# EIB32-JAE-HPC-v2.net
KiCad netlist of a schematic drawn in EAGLE
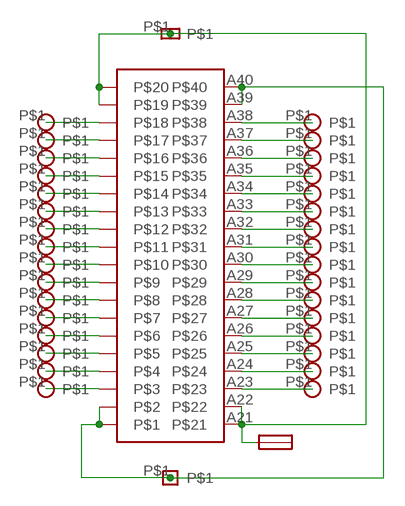
[diagram p0: schematic, sheet 1]

(export (version "E")
  (design (tool "Eeschema 10.0.6"))
  (components
    (comp (ref "U$1")
      (value "WR-40SB-VFH30")
      (footprint "eagle-import:WR-40SB-VFH30")
      (libsource (lib "eagle-import") (part "WR-40SB-VFH30"))
    )
    (comp (ref "U$2")
      (value "EIB-GND-HOLE-PAD-SMALL")
      (footprint "eagle-import:EIB-GND-HOLE-PAD-SMALL")
      (libsource (lib "eagle-import") (part "EIB-GND-HOLE-PAD-SMALL"))
    )
    (comp (ref "U$3")
      (value "EIB-GND-HOLE-PAD")
      (footprint "eagle-import:EIB-GND-HOLE-PAD")
      (libsource (lib "eagle-import") (part "EIB-GND-HOLE-PAD"))
    )
    (comp (ref "U$4")
      (value "JMP-PAD-SMALL")
      (footprint "eagle-import:JMP-PAD-SMALL")
      (libsource (lib "eagle-import") (part "JMP-PAD-SMALL"))
    )
    (comp (ref "U$5")
      (value "EIB-TETRODE-HOLE-RS-PAD")
      (footprint "eagle-import:EIB-TETRODE-HOLE-RS-PAD")
      (libsource (lib "eagle-import") (part "EIB-TETRODE-HOLE-RS-PAD"))
    )
    (comp (ref "U$6")
      (value "EIB-TETRODE-HOLE-RS-PAD")
      (footprint "eagle-import:EIB-TETRODE-HOLE-RS-PAD")
      (libsource (lib "eagle-import") (part "EIB-TETRODE-HOLE-RS-PAD"))
    )
    (comp (ref "U$7")
      (value "EIB-TETRODE-HOLE-RS-PAD")
      (footprint "eagle-import:EIB-TETRODE-HOLE-RS-PAD")
      (libsource (lib "eagle-import") (part "EIB-TETRODE-HOLE-RS-PAD"))
    )
    (comp (ref "U$8")
      (value "EIB-TETRODE-HOLE-RS-PAD")
      (footprint "eagle-import:EIB-TETRODE-HOLE-RS-PAD")
      (libsource (lib "eagle-import") (part "EIB-TETRODE-HOLE-RS-PAD"))
    )
    (comp (ref "U$9")
      (value "EIB-TETRODE-HOLE-RS-PAD")
      (footprint "eagle-import:EIB-TETRODE-HOLE-RS-PAD")
      (libsource (lib "eagle-import") (part "EIB-TETRODE-HOLE-RS-PAD"))
    )
    (comp (ref "U$10")
      (value "EIB-TETRODE-HOLE-RS-PAD")
      (footprint "eagle-import:EIB-TETRODE-HOLE-RS-PAD")
      (libsource (lib "eagle-import") (part "EIB-TETRODE-HOLE-RS-PAD"))
    )
    (comp (ref "U$11")
      (value "EIB-TETRODE-HOLE-RS-PAD")
      (footprint "eagle-import:EIB-TETRODE-HOLE-RS-PAD")
      (libsource (lib "eagle-import") (part "EIB-TETRODE-HOLE-RS-PAD"))
    )
    (comp (ref "U$12")
      (value "EIB-TETRODE-HOLE-RS-PAD")
      (footprint "eagle-import:EIB-TETRODE-HOLE-RS-PAD")
      (libsource (lib "eagle-import") (part "EIB-TETRODE-HOLE-RS-PAD"))
    )
    (comp (ref "U$13")
      (value "EIB-TETRODE-HOLE-RS-PAD")
      (footprint "eagle-import:EIB-TETRODE-HOLE-RS-PAD")
      (libsource (lib "eagle-import") (part "EIB-TETRODE-HOLE-RS-PAD"))
    )
    (comp (ref "U$14")
      (value "EIB-TETRODE-HOLE-RS-PAD")
      (footprint "eagle-import:EIB-TETRODE-HOLE-RS-PAD")
      (libsource (lib "eagle-import") (part "EIB-TETRODE-HOLE-RS-PAD"))
    )
    (comp (ref "U$15")
      (value "EIB-TETRODE-HOLE-RS-PAD")
      (footprint "eagle-import:EIB-TETRODE-HOLE-RS-PAD")
      (libsource (lib "eagle-import") (part "EIB-TETRODE-HOLE-RS-PAD"))
    )
    (comp (ref "U$16")
      (value "EIB-TETRODE-HOLE-RS-PAD")
      (footprint "eagle-import:EIB-TETRODE-HOLE-RS-PAD")
      (libsource (lib "eagle-import") (part "EIB-TETRODE-HOLE-RS-PAD"))
    )
    (comp (ref "U$17")
      (value "EIB-TETRODE-HOLE-RS-PAD")
      (footprint "eagle-import:EIB-TETRODE-HOLE-RS-PAD")
      (libsource (lib "eagle-import") (part "EIB-TETRODE-HOLE-RS-PAD"))
    )
    (comp (ref "U$18")
      (value "EIB-TETRODE-HOLE-RS-PAD")
      (footprint "eagle-import:EIB-TETRODE-HOLE-RS-PAD")
      (libsource (lib "eagle-import") (part "EIB-TETRODE-HOLE-RS-PAD"))
    )
    (comp (ref "U$19")
      (value "EIB-TETRODE-HOLE-RS-PAD")
      (footprint "eagle-import:EIB-TETRODE-HOLE-RS-PAD")
      (libsource (lib "eagle-import") (part "EIB-TETRODE-HOLE-RS-PAD"))
    )
    (comp (ref "U$20")
      (value "EIB-TETRODE-HOLE-RS-PAD")
      (footprint "eagle-import:EIB-TETRODE-HOLE-RS-PAD")
      (libsource (lib "eagle-import") (part "EIB-TETRODE-HOLE-RS-PAD"))
    )
    (comp (ref "U$23")
      (value "EIB-TETRODE-HOLE-RS-PAD")
      (footprint "eagle-import:EIB-TETRODE-HOLE-RS-PAD")
      (libsource (lib "eagle-import") (part "EIB-TETRODE-HOLE-RS-PAD"))
    )
    (comp (ref "U$24")
      (value "EIB-TETRODE-HOLE-RS-PAD")
      (footprint "eagle-import:EIB-TETRODE-HOLE-RS-PAD")
      (libsource (lib "eagle-import") (part "EIB-TETRODE-HOLE-RS-PAD"))
    )
    (comp (ref "U$25")
      (value "EIB-TETRODE-HOLE-RS-PAD")
      (footprint "eagle-import:EIB-TETRODE-HOLE-RS-PAD")
      (libsource (lib "eagle-import") (part "EIB-TETRODE-HOLE-RS-PAD"))
    )
    (comp (ref "U$26")
      (value "EIB-TETRODE-HOLE-RS-PAD")
      (footprint "eagle-import:EIB-TETRODE-HOLE-RS-PAD")
      (libsource (lib "eagle-import") (part "EIB-TETRODE-HOLE-RS-PAD"))
    )
    (comp (ref "U$27")
      (value "EIB-TETRODE-HOLE-RS-PAD")
      (footprint "eagle-import:EIB-TETRODE-HOLE-RS-PAD")
      (libsource (lib "eagle-import") (part "EIB-TETRODE-HOLE-RS-PAD"))
    )
    (comp (ref "U$28")
      (value "EIB-TETRODE-HOLE-RS-PAD")
      (footprint "eagle-import:EIB-TETRODE-HOLE-RS-PAD")
      (libsource (lib "eagle-import") (part "EIB-TETRODE-HOLE-RS-PAD"))
    )
    (comp (ref "U$29")
      (value "EIB-TETRODE-HOLE-RS-PAD")
      (footprint "eagle-import:EIB-TETRODE-HOLE-RS-PAD")
      (libsource (lib "eagle-import") (part "EIB-TETRODE-HOLE-RS-PAD"))
    )
    (comp (ref "U$30")
      (value "EIB-TETRODE-HOLE-RS-PAD")
      (footprint "eagle-import:EIB-TETRODE-HOLE-RS-PAD")
      (libsource (lib "eagle-import") (part "EIB-TETRODE-HOLE-RS-PAD"))
    )
    (comp (ref "U$31")
      (value "EIB-TETRODE-HOLE-RS-PAD")
      (footprint "eagle-import:EIB-TETRODE-HOLE-RS-PAD")
      (libsource (lib "eagle-import") (part "EIB-TETRODE-HOLE-RS-PAD"))
    )
    (comp (ref "U$32")
      (value "EIB-TETRODE-HOLE-RS-PAD")
      (footprint "eagle-import:EIB-TETRODE-HOLE-RS-PAD")
      (libsource (lib "eagle-import") (part "EIB-TETRODE-HOLE-RS-PAD"))
    )
    (comp (ref "U$33")
      (value "EIB-TETRODE-HOLE-RS-PAD")
      (footprint "eagle-import:EIB-TETRODE-HOLE-RS-PAD")
      (libsource (lib "eagle-import") (part "EIB-TETRODE-HOLE-RS-PAD"))
    )
    (comp (ref "U$34")
      (value "EIB-TETRODE-HOLE-RS-PAD")
      (footprint "eagle-import:EIB-TETRODE-HOLE-RS-PAD")
      (libsource (lib "eagle-import") (part "EIB-TETRODE-HOLE-RS-PAD"))
    )
    (comp (ref "U$35")
      (value "EIB-TETRODE-HOLE-RS-PAD")
      (footprint "eagle-import:EIB-TETRODE-HOLE-RS-PAD")
      (libsource (lib "eagle-import") (part "EIB-TETRODE-HOLE-RS-PAD"))
    )
    (comp (ref "U$36")
      (value "EIB-TETRODE-HOLE-RS-PAD")
      (footprint "eagle-import:EIB-TETRODE-HOLE-RS-PAD")
      (libsource (lib "eagle-import") (part "EIB-TETRODE-HOLE-RS-PAD"))
    )
    (comp (ref "U$37")
      (value "EIB-TETRODE-HOLE-RS-PAD")
      (footprint "eagle-import:EIB-TETRODE-HOLE-RS-PAD")
      (libsource (lib "eagle-import") (part "EIB-TETRODE-HOLE-RS-PAD"))
    )
    (comp (ref "U$38")
      (value "EIB-TETRODE-HOLE-RS-PAD")
      (footprint "eagle-import:EIB-TETRODE-HOLE-RS-PAD")
      (libsource (lib "eagle-import") (part "EIB-TETRODE-HOLE-RS-PAD"))
    )
  )
  (nets
    (net (code "1") (name "Net-(U$1-P$1)") (class "Default")
      (node (ref "U$1") (pin "A1") (pinfunction "P$1_A1") (pintype "bidirectional"))
      (node (ref "U$1") (pin "A2") (pinfunction "P$2_A2") (pintype "bidirectional"))
      (node (ref "U$1") (pin "A39") (pinfunction "P$39_A39") (pintype "bidirectional"))
      (node (ref "U$1") (pin "A40") (pinfunction "P$40_A40") (pintype "bidirectional"))
      (node (ref "U$3") (pin "P$1") (pinfunction "P$1_P$1") (pintype "bidirectional"))
    )
    (net (code "2") (name "Net-(U$1-P$3)") (class "Default")
      (node (ref "U$1") (pin "A3") (pinfunction "P$3_A3") (pintype "bidirectional"))
      (node (ref "U$20") (pin "P$1") (pinfunction "P$1_P$1") (pintype "bidirectional"))
    )
    (net (code "3") (name "Net-(U$1-P$4)") (class "Default")
      (node (ref "U$1") (pin "A4") (pinfunction "P$4_A4") (pintype "bidirectional"))
      (node (ref "U$19") (pin "P$1") (pinfunction "P$1_P$1") (pintype "bidirectional"))
    )
    (net (code "4") (name "Net-(U$1-P$5)") (class "Default")
      (node (ref "U$1") (pin "A5") (pinfunction "P$5_A5") (pintype "bidirectional"))
      (node (ref "U$18") (pin "P$1") (pinfunction "P$1_P$1") (pintype "bidirectional"))
    )
    (net (code "5") (name "Net-(U$1-P$6)") (class "Default")
      (node (ref "U$1") (pin "A6") (pinfunction "P$6_A6") (pintype "bidirectional"))
      (node (ref "U$17") (pin "P$1") (pinfunction "P$1_P$1") (pintype "bidirectional"))
    )
    (net (code "6") (name "Net-(U$1-P$7)") (class "Default")
      (node (ref "U$1") (pin "A7") (pinfunction "P$7_A7") (pintype "bidirectional"))
      (node (ref "U$16") (pin "P$1") (pinfunction "P$1_P$1") (pintype "bidirectional"))
    )
    (net (code "7") (name "Net-(U$1-P$8)") (class "Default")
      (node (ref "U$1") (pin "A8") (pinfunction "P$8_A8") (pintype "bidirectional"))
      (node (ref "U$15") (pin "P$1") (pinfunction "P$1_P$1") (pintype "bidirectional"))
    )
    (net (code "8") (name "Net-(U$1-P$9)") (class "Default")
      (node (ref "U$1") (pin "A9") (pinfunction "P$9_A9") (pintype "bidirectional"))
      (node (ref "U$14") (pin "P$1") (pinfunction "P$1_P$1") (pintype "bidirectional"))
    )
    (net (code "9") (name "Net-(U$1-P$10)") (class "Default")
      (node (ref "U$1") (pin "A10") (pinfunction "P$10_A10") (pintype "bidirectional"))
      (node (ref "U$13") (pin "P$1") (pinfunction "P$1_P$1") (pintype "bidirectional"))
    )
    (net (code "10") (name "Net-(U$1-P$11)") (class "Default")
      (node (ref "U$1") (pin "A11") (pinfunction "P$11_A11") (pintype "bidirectional"))
      (node (ref "U$12") (pin "P$1") (pinfunction "P$1_P$1") (pintype "bidirectional"))
    )
    (net (code "11") (name "Net-(U$1-P$12)") (class "Default")
      (node (ref "U$1") (pin "A12") (pinfunction "P$12_A12") (pintype "bidirectional"))
      (node (ref "U$11") (pin "P$1") (pinfunction "P$1_P$1") (pintype "bidirectional"))
    )
    (net (code "12") (name "Net-(U$1-P$13)") (class "Default")
      (node (ref "U$1") (pin "A13") (pinfunction "P$13_A13") (pintype "bidirectional"))
      (node (ref "U$10") (pin "P$1") (pinfunction "P$1_P$1") (pintype "bidirectional"))
    )
    (net (code "13") (name "Net-(U$1-P$14)") (class "Default")
      (node (ref "U$1") (pin "A14") (pinfunction "P$14_A14") (pintype "bidirectional"))
      (node (ref "U$9") (pin "P$1") (pinfunction "P$1_P$1") (pintype "bidirectional"))
    )
    (net (code "14") (name "Net-(U$1-P$15)") (class "Default")
      (node (ref "U$1") (pin "A15") (pinfunction "P$15_A15") (pintype "bidirectional"))
      (node (ref "U$8") (pin "P$1") (pinfunction "P$1_P$1") (pintype "bidirectional"))
    )
    (net (code "15") (name "Net-(U$1-P$16)") (class "Default")
      (node (ref "U$1") (pin "A16") (pinfunction "P$16_A16") (pintype "bidirectional"))
      (node (ref "U$7") (pin "P$1") (pinfunction "P$1_P$1") (pintype "bidirectional"))
    )
    (net (code "16") (name "Net-(U$1-P$17)") (class "Default")
      (node (ref "U$1") (pin "A17") (pinfunction "P$17_A17") (pintype "bidirectional"))
      (node (ref "U$6") (pin "P$1") (pinfunction "P$1_P$1") (pintype "bidirectional"))
    )
    (net (code "17") (name "Net-(U$1-P$18)") (class "Default")
      (node (ref "U$1") (pin "A18") (pinfunction "P$18_A18") (pintype "bidirectional"))
      (node (ref "U$5") (pin "P$1") (pinfunction "P$1_P$1") (pintype "bidirectional"))
    )
    (net (code "18") (name "Net-(U$1-P$19)") (class "Default")
      (node (ref "U$1") (pin "A19") (pinfunction "P$19_A19") (pintype "bidirectional"))
      (node (ref "U$1") (pin "A20") (pinfunction "P$20_A20") (pintype "bidirectional"))
      (node (ref "U$1") (pin "A21") (pinfunction "P$21_A21") (pintype "bidirectional"))
      (node (ref "U$1") (pin "A22") (pinfunction "P$22_A22") (pintype "bidirectional"))
      (node (ref "U$2") (pin "P$1") (pinfunction "P$1_P$1") (pintype "bidirectional"))
      (node (ref "U$4") (pin "P$1") (pinfunction "P$1_P$1") (pintype "bidirectional"))
    )
    (net (code "19") (name "Net-(U$1-P$23)") (class "Default")
      (node (ref "U$1") (pin "A23") (pinfunction "P$23_A23") (pintype "bidirectional"))
      (node (ref "U$38") (pin "P$1") (pinfunction "P$1_P$1") (pintype "bidirectional"))
    )
    (net (code "20") (name "Net-(U$1-P$24)") (class "Default")
      (node (ref "U$1") (pin "A24") (pinfunction "P$24_A24") (pintype "bidirectional"))
      (node (ref "U$37") (pin "P$1") (pinfunction "P$1_P$1") (pintype "bidirectional"))
    )
    (net (code "21") (name "Net-(U$1-P$25)") (class "Default")
      (node (ref "U$1") (pin "A25") (pinfunction "P$25_A25") (pintype "bidirectional"))
      (node (ref "U$36") (pin "P$1") (pinfunction "P$1_P$1") (pintype "bidirectional"))
    )
    (net (code "22") (name "Net-(U$1-P$26)") (class "Default")
      (node (ref "U$1") (pin "A26") (pinfunction "P$26_A26") (pintype "bidirectional"))
      (node (ref "U$35") (pin "P$1") (pinfunction "P$1_P$1") (pintype "bidirectional"))
    )
    (net (code "23") (name "Net-(U$1-P$27)") (class "Default")
      (node (ref "U$1") (pin "A27") (pinfunction "P$27_A27") (pintype "bidirectional"))
      (node (ref "U$34") (pin "P$1") (pinfunction "P$1_P$1") (pintype "bidirectional"))
    )
    (net (code "24") (name "Net-(U$1-P$28)") (class "Default")
      (node (ref "U$1") (pin "A28") (pinfunction "P$28_A28") (pintype "bidirectional"))
      (node (ref "U$33") (pin "P$1") (pinfunction "P$1_P$1") (pintype "bidirectional"))
    )
    (net (code "25") (name "Net-(U$1-P$29)") (class "Default")
      (node (ref "U$1") (pin "A29") (pinfunction "P$29_A29") (pintype "bidirectional"))
      (node (ref "U$32") (pin "P$1") (pinfunction "P$1_P$1") (pintype "bidirectional"))
    )
    (net (code "26") (name "Net-(U$1-P$30)") (class "Default")
      (node (ref "U$1") (pin "A30") (pinfunction "P$30_A30") (pintype "bidirectional"))
      (node (ref "U$31") (pin "P$1") (pinfunction "P$1_P$1") (pintype "bidirectional"))
    )
    (net (code "27") (name "Net-(U$1-P$31)") (class "Default")
      (node (ref "U$1") (pin "A31") (pinfunction "P$31_A31") (pintype "bidirectional"))
      (node (ref "U$30") (pin "P$1") (pinfunction "P$1_P$1") (pintype "bidirectional"))
    )
    (net (code "28") (name "Net-(U$1-P$32)") (class "Default")
      (node (ref "U$1") (pin "A32") (pinfunction "P$32_A32") (pintype "bidirectional"))
      (node (ref "U$29") (pin "P$1") (pinfunction "P$1_P$1") (pintype "bidirectional"))
    )
    (net (code "29") (name "Net-(U$1-P$33)") (class "Default")
      (node (ref "U$1") (pin "A33") (pinfunction "P$33_A33") (pintype "bidirectional"))
      (node (ref "U$28") (pin "P$1") (pinfunction "P$1_P$1") (pintype "bidirectional"))
    )
    (net (code "30") (name "Net-(U$1-P$34)") (class "Default")
      (node (ref "U$1") (pin "A34") (pinfunction "P$34_A34") (pintype "bidirectional"))
      (node (ref "U$27") (pin "P$1") (pinfunction "P$1_P$1") (pintype "bidirectional"))
    )
    (net (code "31") (name "Net-(U$1-P$35)") (class "Default")
      (node (ref "U$1") (pin "A35") (pinfunction "P$35_A35") (pintype "bidirectional"))
      (node (ref "U$26") (pin "P$1") (pinfunction "P$1_P$1") (pintype "bidirectional"))
    )
    (net (code "32") (name "Net-(U$1-P$36)") (class "Default")
      (node (ref "U$1") (pin "A36") (pinfunction "P$36_A36") (pintype "bidirectional"))
      (node (ref "U$25") (pin "P$1") (pinfunction "P$1_P$1") (pintype "bidirectional"))
    )
    (net (code "33") (name "Net-(U$1-P$37)") (class "Default")
      (node (ref "U$1") (pin "A37") (pinfunction "P$37_A37") (pintype "bidirectional"))
      (node (ref "U$24") (pin "P$1") (pinfunction "P$1_P$1") (pintype "bidirectional"))
    )
    (net (code "34") (name "Net-(U$1-P$38)") (class "Default")
      (node (ref "U$1") (pin "A38") (pinfunction "P$38_A38") (pintype "bidirectional"))
      (node (ref "U$23") (pin "P$1") (pinfunction "P$1_P$1") (pintype "bidirectional"))
    )
  )
)
